# CellRev4.net
KiCad netlist of a schematic drawn in EAGLE
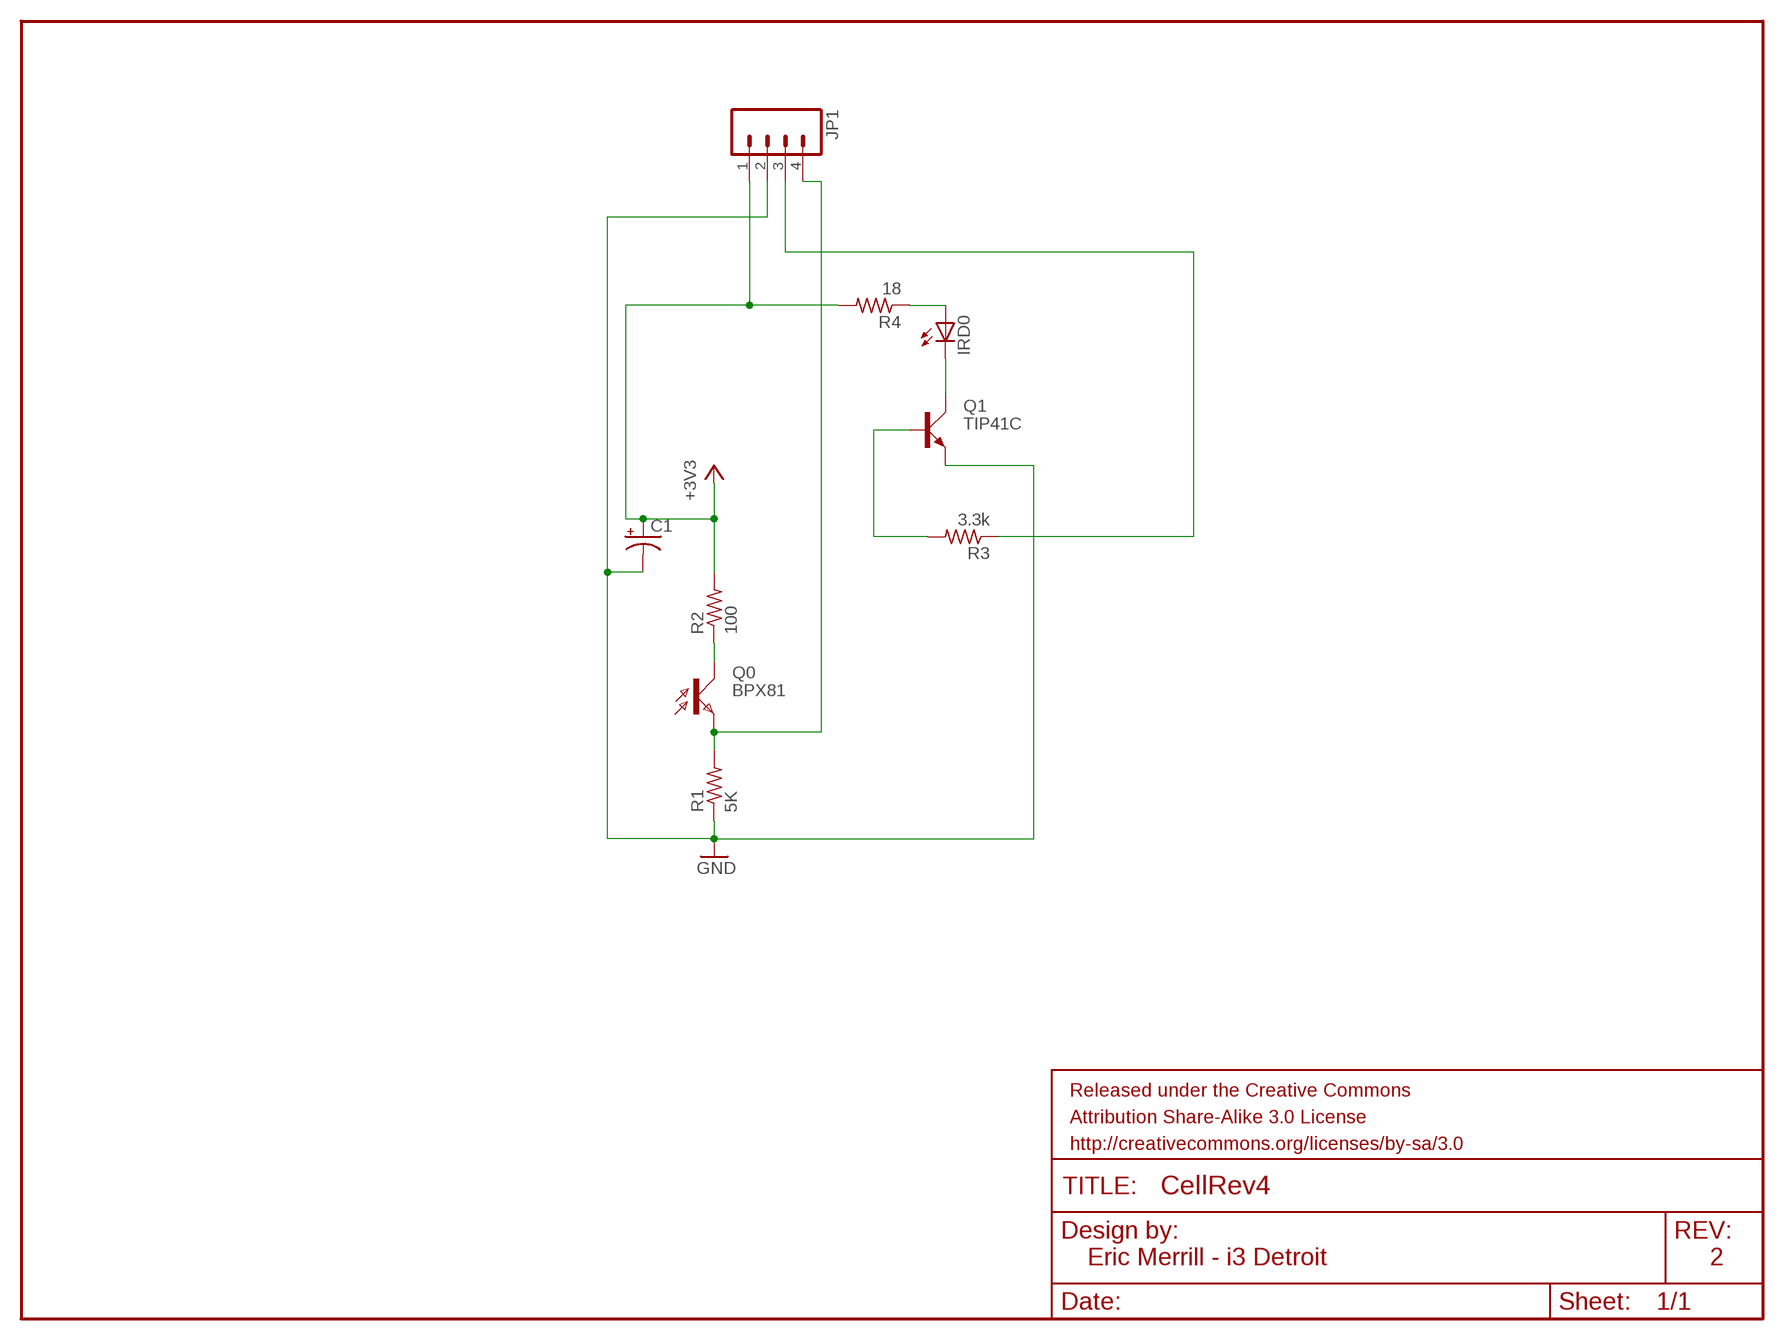
[diagram p0: schematic, sheet 1]

(export (version "E")
  (design (tool "Eeschema 10.0.6"))
  (components
    (comp (ref "C1")
      (value "CAP_POLPTH1")
      (footprint "eagle-import:CPOL-RADIAL-100UF-25V")
      (libsource (lib "eagle-import") (part "CAP_POLPTH1"))
    )
    (comp (ref "FRAME1")
      (value "FRAME-LETTER")
      (footprint "eagle-import:CREATIVE_COMMONS")
      (libsource (lib "eagle-import") (part "FRAME-LETTER"))
    )
    (comp (ref "IRD0")
      (value "LED5MM")
      (footprint "eagle-import:LED5MM")
      (libsource (lib "eagle-import") (part "LED5MM"))
    )
    (comp (ref "JP1")
      (value "M04POLAR")
      (footprint "eagle-import:MOLEX-1X4")
      (libsource (lib "eagle-import") (part "M04POLAR"))
    )
    (comp (ref "Q0")
      (value "BPX81")
      (footprint "eagle-import:BPX81")
      (libsource (lib "eagle-import") (part "BPX81"))
    )
    (comp (ref "Q1")
      (value "TIP41C")
      (footprint "eagle-import:TO220AV")
      (libsource (lib "eagle-import") (part "TIP41C"))
    )
    (comp (ref "R1")
      (value "5K")
      (footprint "eagle-import:0207_10")
      (libsource (lib "eagle-import") (part "R-US_0207/10"))
    )
    (comp (ref "R2")
      (value "100")
      (footprint "eagle-import:0207_10")
      (libsource (lib "eagle-import") (part "R-US_0207/10"))
    )
    (comp (ref "R3")
      (value "3.3k")
      (footprint "eagle-import:0207_10")
      (libsource (lib "eagle-import") (part "R-US_0207/10"))
    )
    (comp (ref "R4")
      (value "18")
      (footprint "eagle-import:0207_10")
      (libsource (lib "eagle-import") (part "R-US_0207/10"))
    )
  )
  (nets
    (net (code "1") (name "+3V3") (class "Default")
      (node (ref "C1") (pin "1") (pinfunction "+_1") (pintype "passive"))
      (node (ref "JP1") (pin "1") (pinfunction "1_1") (pintype "passive"))
      (node (ref "R2") (pin "2") (pinfunction "2_2") (pintype "passive"))
      (node (ref "R4") (pin "2") (pinfunction "2_2") (pintype "passive"))
    )
    (net (code "2") (name "GND") (class "Default")
      (node (ref "C1") (pin "2") (pinfunction "-_2") (pintype "passive"))
      (node (ref "JP1") (pin "2") (pinfunction "2_2") (pintype "passive"))
      (node (ref "Q1") (pin "E") (pinfunction "E_E") (pintype "passive"))
      (node (ref "R1") (pin "1") (pinfunction "1_1") (pintype "passive"))
    )
    (net (code "3") (name "Net-(IRD0-C)") (class "Default")
      (node (ref "IRD0") (pin "K") (pinfunction "C_K") (pintype "passive"))
      (node (ref "Q1") (pin "C") (pinfunction "C_C") (pintype "passive"))
    )
    (net (code "4") (name "Net-(IRD0-PadA)") (class "Default")
      (node (ref "IRD0") (pin "A") (pinfunction "A_A") (pintype "passive"))
      (node (ref "R4") (pin "1") (pinfunction "1_1") (pintype "passive"))
    )
    (net (code "5") (name "Net-(JP1-Pad3)") (class "Default")
      (node (ref "JP1") (pin "3") (pinfunction "3_3") (pintype "passive"))
      (node (ref "R3") (pin "1") (pinfunction "1_1") (pintype "passive"))
    )
    (net (code "6") (name "Net-(JP1-Pad4)") (class "Default")
      (node (ref "JP1") (pin "4") (pinfunction "4_4") (pintype "passive"))
      (node (ref "Q0") (pin "E") (pinfunction "E_E") (pintype "passive"))
      (node (ref "R1") (pin "2") (pinfunction "2_2") (pintype "passive"))
    )
    (net (code "7") (name "Net-(Q0-PadC)") (class "Default")
      (node (ref "Q0") (pin "C") (pinfunction "C_C") (pintype "passive"))
      (node (ref "R2") (pin "1") (pinfunction "1_1") (pintype "passive"))
    )
    (net (code "8") (name "Net-(Q1-PadB)") (class "Default")
      (node (ref "Q1") (pin "B") (pinfunction "B_B") (pintype "passive"))
      (node (ref "R3") (pin "2") (pinfunction "2_2") (pintype "passive"))
    )
  )
)
